# telemetry.net
KiCad netlist of a schematic drawn in EAGLE
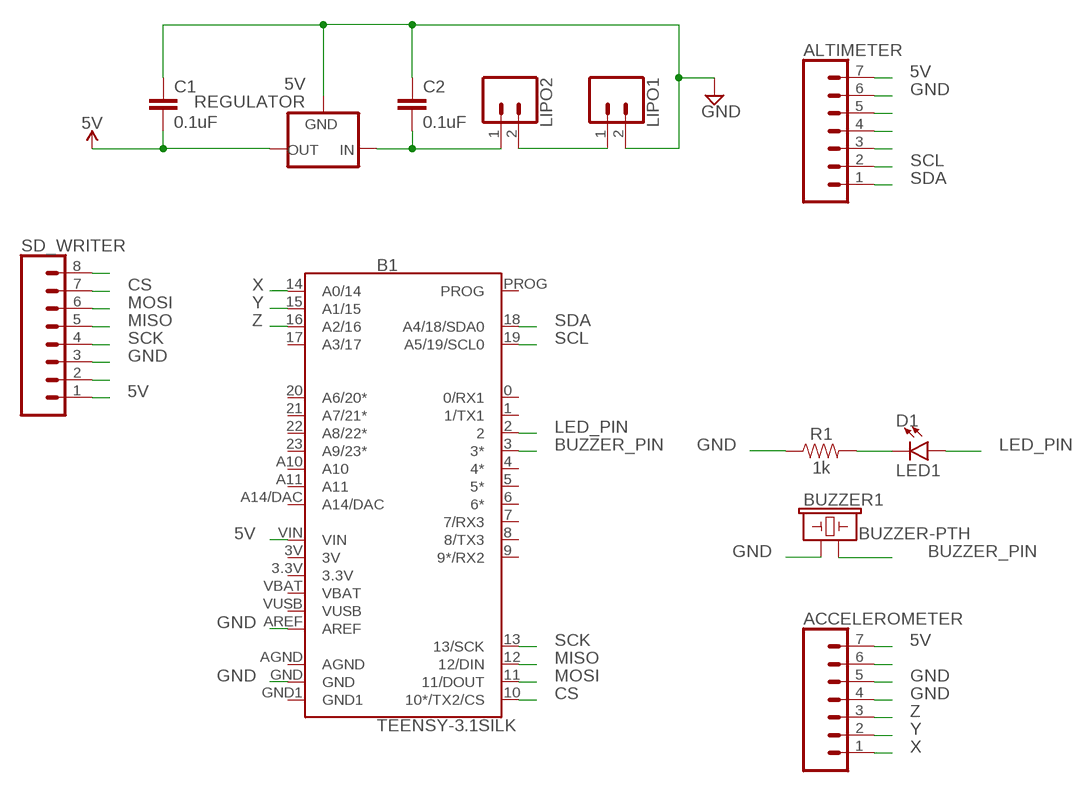
[diagram p0: schematic, sheet 1]

(export (version "E")
  (design (tool "Eeschema 10.0.6"))
  (components
    (comp (ref "ACCELEROMETER")
      (value "CONN_07")
      (footprint "eagle-import:1X07")
      (libsource (lib "eagle-import") (part "CONN_07"))
    )
    (comp (ref "ALTIMETER")
      (value "CONN_07")
      (footprint "eagle-import:1X07")
      (libsource (lib "eagle-import") (part "CONN_07"))
    )
    (comp (ref "B1")
      (value "TEENSY-3.1SILK")
      (footprint "eagle-import:TEENSY-3.1")
      (libsource (lib "eagle-import") (part "TEENSY-3.1SILK"))
    )
    (comp (ref "BUZZER1")
      (value "BUZZER-PTH")
      (footprint "eagle-import:BUZZER-12MM")
      (libsource (lib "eagle-import") (part "BUZZER-PTH"))
    )
    (comp (ref "C1")
      (value "0.1uF")
      (footprint "eagle-import:CAP-PTH-SMALL-KIT")
      (libsource (lib "eagle-import") (part "0.1UF-KIT-EZ-50V-20%"))
    )
    (comp (ref "C2")
      (value "0.1uF")
      (footprint "eagle-import:CAP-PTH-SMALL-KIT")
      (libsource (lib "eagle-import") (part "0.1UF-KIT-EZ-50V-20%"))
    )
    (comp (ref "D1")
      (value "LED1")
      (footprint "eagle-import:LED_5MM")
      (libsource (lib "eagle-import") (part "LED5MM"))
    )
    (comp (ref "LIPO1")
      (value "CONN_02")
      (footprint "eagle-import:1X02")
      (libsource (lib "eagle-import") (part "CONN_02"))
    )
    (comp (ref "LIPO2")
      (value "CONN_02")
      (footprint "eagle-import:1X02")
      (libsource (lib "eagle-import") (part "CONN_02"))
    )
    (comp (ref "R1")
      (value "1k")
      (footprint "eagle-import:AXIAL-0.3")
      (libsource (lib "eagle-import") (part "1KOHM-HORIZ-1/4W-1%"))
    )
    (comp (ref "REGULATOR")
      (value "5V")
      (footprint "eagle-import:78XXS")
      (libsource (lib "eagle-import") (part "78XXS"))
    )
    (comp (ref "SD_WRITER")
      (value "CONN_08\"")
      (footprint "eagle-import:1X08")
      (libsource (lib "eagle-import") (part "CONN_08{dblquote}"))
    )
  )
  (nets
    (net (code "1") (name "/3.3V") (class "Default")
      (node (ref "B1") (pin "3.3V") (pinfunction "3.3V_3.3V") (pintype "power_in"))
    )
    (net (code "2") (name "/3V") (class "Default")
      (node (ref "B1") (pin "3V") (pinfunction "3V_3V") (pintype "power_in"))
    )
    (net (code "3") (name "/AGND") (class "Default")
      (node (ref "B1") (pin "AGND") (pinfunction "AGND_AGND") (pintype "power_in"))
    )
    (net (code "4") (name "/BUZZER_PIN") (class "Default")
      (node (ref "B1") (pin "3") (pinfunction "3*_3") (pintype "bidirectional"))
      (node (ref "BUZZER1") (pin "-") (pinfunction "2_-") (pintype "passive"))
    )
    (net (code "5") (name "/CS") (class "Default")
      (node (ref "B1") (pin "10") (pinfunction "10*/TX2/CS_10") (pintype "bidirectional"))
      (node (ref "SD_WRITER") (pin "7") (pinfunction "7_7") (pintype "passive"))
    )
    (net (code "6") (name "/GND1") (class "Default")
      (node (ref "B1") (pin "GND1") (pinfunction "GND1_GND1") (pintype "power_in"))
    )
    (net (code "7") (name "/LED_PIN") (class "Default")
      (node (ref "B1") (pin "2") (pinfunction "2_2") (pintype "bidirectional"))
      (node (ref "D1") (pin "A") (pinfunction "A_A") (pintype "passive"))
    )
    (net (code "8") (name "/MISO") (class "Default")
      (node (ref "B1") (pin "12") (pinfunction "12/DIN_12") (pintype "bidirectional"))
      (node (ref "SD_WRITER") (pin "5") (pinfunction "5_5") (pintype "passive"))
    )
    (net (code "9") (name "/MOSI") (class "Default")
      (node (ref "B1") (pin "11") (pinfunction "11/DOUT_11") (pintype "bidirectional"))
      (node (ref "SD_WRITER") (pin "6") (pinfunction "6_6") (pintype "passive"))
    )
    (net (code "10") (name "/SCK") (class "Default")
      (node (ref "B1") (pin "13") (pinfunction "13/SCK_13") (pintype "bidirectional"))
      (node (ref "SD_WRITER") (pin "4") (pinfunction "4_4") (pintype "passive"))
    )
    (net (code "11") (name "/SCL") (class "Default")
      (node (ref "ALTIMETER") (pin "2") (pinfunction "2_2") (pintype "passive"))
      (node (ref "B1") (pin "19") (pinfunction "A5/19/SCL0_19") (pintype "bidirectional"))
    )
    (net (code "12") (name "/SDA") (class "Default")
      (node (ref "ALTIMETER") (pin "1") (pinfunction "1_1") (pintype "passive"))
      (node (ref "B1") (pin "18") (pinfunction "A4/18/SDA0_18") (pintype "bidirectional"))
    )
    (net (code "13") (name "/VBAT") (class "Default")
      (node (ref "B1") (pin "VBAT") (pinfunction "VBAT_VBAT") (pintype "power_in"))
    )
    (net (code "14") (name "/VUSB") (class "Default")
      (node (ref "B1") (pin "VUSB") (pinfunction "VUSB_VUSB") (pintype "power_in"))
    )
    (net (code "15") (name "/X") (class "Default")
      (node (ref "ACCELEROMETER") (pin "1") (pinfunction "1_1") (pintype "passive"))
      (node (ref "B1") (pin "14") (pinfunction "A0/14_14") (pintype "bidirectional"))
    )
    (net (code "16") (name "/Y") (class "Default")
      (node (ref "ACCELEROMETER") (pin "2") (pinfunction "2_2") (pintype "passive"))
      (node (ref "B1") (pin "15") (pinfunction "A1/15_15") (pintype "bidirectional"))
    )
    (net (code "17") (name "/Z") (class "Default")
      (node (ref "ACCELEROMETER") (pin "3") (pinfunction "3_3") (pintype "passive"))
      (node (ref "B1") (pin "16") (pinfunction "A2/16_16") (pintype "bidirectional"))
    )
    (net (code "18") (name "5V") (class "Default")
      (node (ref "ACCELEROMETER") (pin "7") (pinfunction "7_7") (pintype "passive"))
      (node (ref "ALTIMETER") (pin "7") (pinfunction "7_7") (pintype "passive"))
      (node (ref "B1") (pin "VIN") (pinfunction "VIN_VIN") (pintype "power_in"))
      (node (ref "C1") (pin "2") (pinfunction "2_2") (pintype "passive"))
      (node (ref "REGULATOR") (pin "OUT") (pinfunction "OUT_OUT") (pintype "passive"))
      (node (ref "SD_WRITER") (pin "1") (pinfunction "1_1") (pintype "passive"))
    )
    (net (code "19") (name "GND") (class "Default")
      (node (ref "ACCELEROMETER") (pin "4") (pinfunction "4_4") (pintype "passive"))
      (node (ref "ACCELEROMETER") (pin "5") (pinfunction "5_5") (pintype "passive"))
      (node (ref "ALTIMETER") (pin "6") (pinfunction "6_6") (pintype "passive"))
      (node (ref "B1") (pin "AREF") (pinfunction "AREF_AREF") (pintype "bidirectional"))
      (node (ref "B1") (pin "GND") (pinfunction "GND_GND") (pintype "power_in"))
      (node (ref "BUZZER1") (pin "+") (pinfunction "1_+") (pintype "passive"))
      (node (ref "C1") (pin "1") (pinfunction "1_1") (pintype "passive"))
      (node (ref "C2") (pin "1") (pinfunction "1_1") (pintype "passive"))
      (node (ref "LIPO1") (pin "2") (pinfunction "2_2") (pintype "passive"))
      (node (ref "R1") (pin "P$1") (pinfunction "1_P$1") (pintype "passive"))
      (node (ref "REGULATOR") (pin "GND") (pinfunction "GND_GND") (pintype "input"))
      (node (ref "SD_WRITER") (pin "3") (pinfunction "3_3") (pintype "passive"))
    )
    (net (code "20") (name "Net-(C2-Pad2)") (class "Default")
      (node (ref "C2") (pin "2") (pinfunction "2_2") (pintype "passive"))
      (node (ref "LIPO2") (pin "1") (pinfunction "1_1") (pintype "passive"))
      (node (ref "REGULATOR") (pin "IN") (pinfunction "IN_IN") (pintype "input"))
    )
    (net (code "21") (name "Net-(D1-C)") (class "Default")
      (node (ref "D1") (pin "K") (pinfunction "C_K") (pintype "passive"))
      (node (ref "R1") (pin "P$2") (pinfunction "2_P$2") (pintype "passive"))
    )
    (net (code "22") (name "Net-(LIPO1-Pad1)") (class "Default")
      (node (ref "LIPO1") (pin "1") (pinfunction "1_1") (pintype "passive"))
      (node (ref "LIPO2") (pin "2") (pinfunction "2_2") (pintype "passive"))
    )
    (net (code "23") (name "unconnected-(ACCELEROMETER-Pad6)") (class "Default")
      (node (ref "ACCELEROMETER") (pin "6") (pinfunction "6_6") (pintype "passive"))
    )
    (net (code "24") (name "unconnected-(ALTIMETER-Pad3)") (class "Default")
      (node (ref "ALTIMETER") (pin "3") (pinfunction "3_3") (pintype "passive"))
    )
    (net (code "25") (name "unconnected-(ALTIMETER-Pad4)") (class "Default")
      (node (ref "ALTIMETER") (pin "4") (pinfunction "4_4") (pintype "passive"))
    )
    (net (code "26") (name "unconnected-(ALTIMETER-Pad5)") (class "Default")
      (node (ref "ALTIMETER") (pin "5") (pinfunction "5_5") (pintype "passive"))
    )
    (net (code "27") (name "unconnected-(B1-0{slash}RX1-Pad0)") (class "Default")
      (node (ref "B1") (pin "0") (pinfunction "0/RX1_0") (pintype "bidirectional"))
    )
    (net (code "28") (name "unconnected-(B1-1{slash}TX1-Pad1)") (class "Default")
      (node (ref "B1") (pin "1") (pinfunction "1/TX1_1") (pintype "bidirectional"))
    )
    (net (code "29") (name "unconnected-(B1-4*-Pad4)") (class "Default")
      (node (ref "B1") (pin "4") (pinfunction "4*_4") (pintype "bidirectional"))
    )
    (net (code "30") (name "unconnected-(B1-5*-Pad5)") (class "Default")
      (node (ref "B1") (pin "5") (pinfunction "5*_5") (pintype "bidirectional"))
    )
    (net (code "31") (name "unconnected-(B1-6*-Pad6)") (class "Default")
      (node (ref "B1") (pin "6") (pinfunction "6*_6") (pintype "bidirectional"))
    )
    (net (code "32") (name "unconnected-(B1-7{slash}RX3-Pad7)") (class "Default")
      (node (ref "B1") (pin "7") (pinfunction "7/RX3_7") (pintype "bidirectional"))
    )
    (net (code "33") (name "unconnected-(B1-8{slash}TX3-Pad8)") (class "Default")
      (node (ref "B1") (pin "8") (pinfunction "8/TX3_8") (pintype "bidirectional"))
    )
    (net (code "34") (name "unconnected-(B1-9*{slash}RX2-Pad9)") (class "Default")
      (node (ref "B1") (pin "9") (pinfunction "9*/RX2_9") (pintype "bidirectional"))
    )
    (net (code "35") (name "unconnected-(B1-A3{slash}17-Pad17)") (class "Default")
      (node (ref "B1") (pin "17") (pinfunction "A3/17_17") (pintype "bidirectional"))
    )
    (net (code "36") (name "unconnected-(B1-A6{slash}20*-Pad20)") (class "Default")
      (node (ref "B1") (pin "20") (pinfunction "A6/20*_20") (pintype "bidirectional"))
    )
    (net (code "37") (name "unconnected-(B1-A7{slash}21*-Pad21)") (class "Default")
      (node (ref "B1") (pin "21") (pinfunction "A7/21*_21") (pintype "bidirectional"))
    )
    (net (code "38") (name "unconnected-(B1-A8{slash}22*-Pad22)") (class "Default")
      (node (ref "B1") (pin "22") (pinfunction "A8/22*_22") (pintype "bidirectional"))
    )
    (net (code "39") (name "unconnected-(B1-A9{slash}23*-Pad23)") (class "Default")
      (node (ref "B1") (pin "23") (pinfunction "A9/23*_23") (pintype "bidirectional"))
    )
    (net (code "40") (name "unconnected-(B1-PadA10)") (class "Default")
      (node (ref "B1") (pin "A10") (pinfunction "A10_A10") (pintype "bidirectional"))
    )
    (net (code "41") (name "unconnected-(B1-PadA11)") (class "Default")
      (node (ref "B1") (pin "A11") (pinfunction "A11_A11") (pintype "bidirectional"))
    )
    (net (code "42") (name "unconnected-(B1-PadA14{slash}DAC)") (class "Default")
      (node (ref "B1") (pin "A14/DAC") (pinfunction "A14/DAC_A14/DAC") (pintype "bidirectional"))
    )
    (net (code "43") (name "unconnected-(B1-PadPROG)") (class "Default")
      (node (ref "B1") (pin "PROG") (pinfunction "PROG_PROG") (pintype "bidirectional"))
    )
    (net (code "44") (name "unconnected-(SD_WRITER-Pad2)") (class "Default")
      (node (ref "SD_WRITER") (pin "2") (pinfunction "2_2") (pintype "passive"))
    )
    (net (code "45") (name "unconnected-(SD_WRITER-Pad8)") (class "Default")
      (node (ref "SD_WRITER") (pin "8") (pinfunction "8_8") (pintype "passive"))
    )
  )
)
